# Ad8232_placa_V3.net
KiCad netlist of a schematic drawn in EAGLE
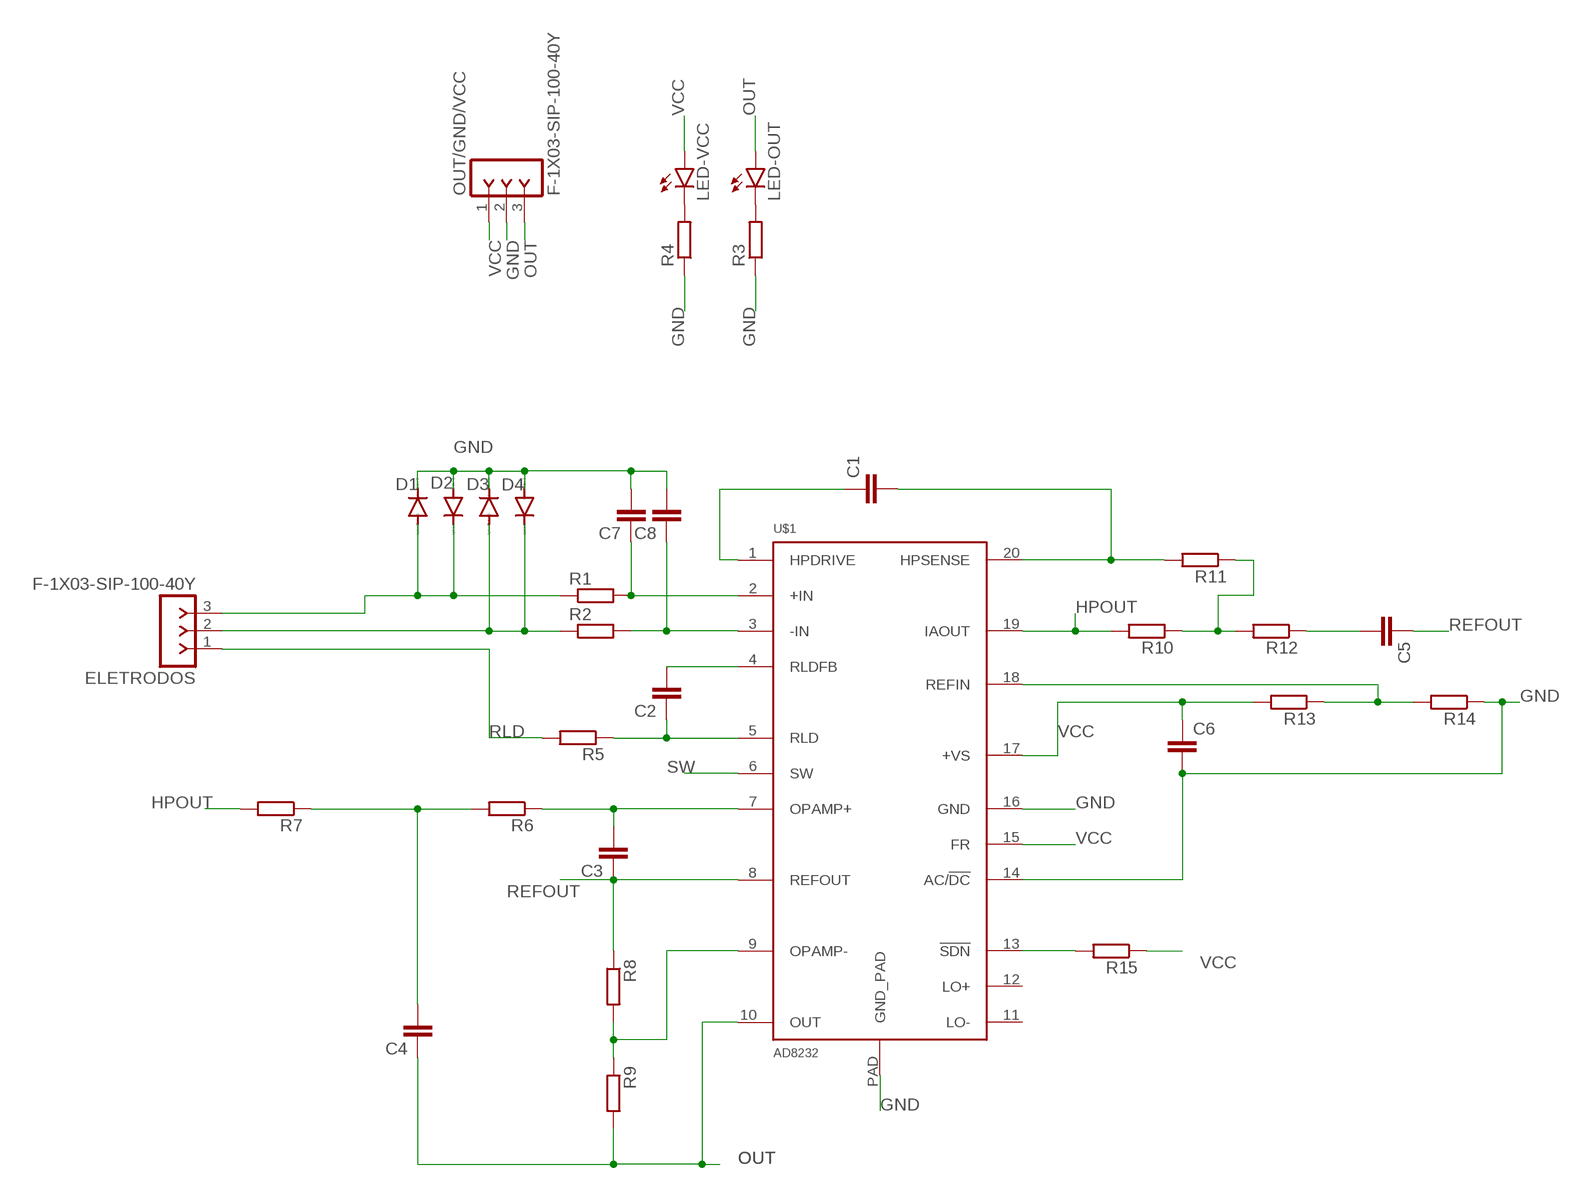
[diagram p0: schematic, sheet 1]

(export (version "E")
  (design (tool "Eeschema 10.0.6"))
  (components
    (comp (ref "C1")
      (value "C-EUC0805")
      (footprint "eagle-import:C0805")
      (libsource (lib "eagle-import") (part "C-EUC0805"))
    )
    (comp (ref "C2")
      (value "C-EUC0805")
      (footprint "eagle-import:C0805")
      (libsource (lib "eagle-import") (part "C-EUC0805"))
    )
    (comp (ref "C3")
      (value "C-EUC0805")
      (footprint "eagle-import:C0805")
      (libsource (lib "eagle-import") (part "C-EUC0805"))
    )
    (comp (ref "C4")
      (value "C-EUC0805")
      (footprint "eagle-import:C0805")
      (libsource (lib "eagle-import") (part "C-EUC0805"))
    )
    (comp (ref "C5")
      (value "C-EUC0805")
      (footprint "eagle-import:C0805")
      (libsource (lib "eagle-import") (part "C-EUC0805"))
    )
    (comp (ref "C6")
      (value "C-EUC0805")
      (footprint "eagle-import:C0805")
      (libsource (lib "eagle-import") (part "C-EUC0805"))
    )
    (comp (ref "C7")
      (value "C-EUC0805")
      (footprint "eagle-import:C0805")
      (libsource (lib "eagle-import") (part "C-EUC0805"))
    )
    (comp (ref "C8")
      (value "C-EUC0805")
      (footprint "eagle-import:C0805")
      (libsource (lib "eagle-import") (part "C-EUC0805"))
    )
    (comp (ref "D1")
      (value "DIODE-MINIMELF")
      (footprint "eagle-import:MINIMELF")
      (libsource (lib "eagle-import") (part "DIODE-MINIMELF"))
    )
    (comp (ref "D2")
      (value "DIODE-MINIMELF")
      (footprint "eagle-import:MINIMELF")
      (libsource (lib "eagle-import") (part "DIODE-MINIMELF"))
    )
    (comp (ref "D3")
      (value "DIODE-MINIMELF")
      (footprint "eagle-import:MINIMELF")
      (libsource (lib "eagle-import") (part "DIODE-MINIMELF"))
    )
    (comp (ref "D4")
      (value "DIODE-MINIMELF")
      (footprint "eagle-import:MINIMELF")
      (libsource (lib "eagle-import") (part "DIODE-MINIMELF"))
    )
    (comp (ref "ELETRODOS")
      (value "F-1X03-SIP-100-40Y")
      (footprint "eagle-import:SIP-100-03-40Y")
      (libsource (lib "eagle-import") (part "F-1X03-SIP-100-40Y"))
    )
    (comp (ref "LED-OUT")
      (value "LEDCHIPLED_0603")
      (footprint "eagle-import:CHIPLED_0603")
      (libsource (lib "eagle-import") (part "LEDCHIPLED_0603"))
    )
    (comp (ref "LED-VCC")
      (value "LEDCHIPLED_0603")
      (footprint "eagle-import:CHIPLED_0603")
      (libsource (lib "eagle-import") (part "LEDCHIPLED_0603"))
    )
    (comp (ref "OUT/GND/VCC")
      (value "F-1X03-SIP-100-40Y")
      (footprint "eagle-import:SIP-100-03-40Y")
      (libsource (lib "eagle-import") (part "F-1X03-SIP-100-40Y"))
    )
    (comp (ref "R1")
      (value "R-EU_R0805")
      (footprint "eagle-import:R0805")
      (libsource (lib "eagle-import") (part "R-EU_R0805"))
    )
    (comp (ref "R2")
      (value "R-EU_R0805")
      (footprint "eagle-import:R0805")
      (libsource (lib "eagle-import") (part "R-EU_R0805"))
    )
    (comp (ref "R3")
      (value "R-EU_R0805")
      (footprint "eagle-import:R0805")
      (libsource (lib "eagle-import") (part "R-EU_R0805"))
    )
    (comp (ref "R4")
      (value "R-EU_R0805")
      (footprint "eagle-import:R0805")
      (libsource (lib "eagle-import") (part "R-EU_R0805"))
    )
    (comp (ref "R5")
      (value "R-EU_R0805")
      (footprint "eagle-import:R0805")
      (libsource (lib "eagle-import") (part "R-EU_R0805"))
    )
    (comp (ref "R6")
      (value "R-EU_R0805")
      (footprint "eagle-import:R0805")
      (libsource (lib "eagle-import") (part "R-EU_R0805"))
    )
    (comp (ref "R7")
      (value "R-EU_R0805")
      (footprint "eagle-import:R0805")
      (libsource (lib "eagle-import") (part "R-EU_R0805"))
    )
    (comp (ref "R8")
      (value "R-EU_R0805")
      (footprint "eagle-import:R0805")
      (libsource (lib "eagle-import") (part "R-EU_R0805"))
    )
    (comp (ref "R9")
      (value "R-EU_R0805")
      (footprint "eagle-import:R0805")
      (libsource (lib "eagle-import") (part "R-EU_R0805"))
    )
    (comp (ref "R10")
      (value "R-EU_R0805")
      (footprint "eagle-import:R0805")
      (libsource (lib "eagle-import") (part "R-EU_R0805"))
    )
    (comp (ref "R11")
      (value "R-EU_R0805")
      (footprint "eagle-import:R0805")
      (libsource (lib "eagle-import") (part "R-EU_R0805"))
    )
    (comp (ref "R12")
      (value "R-EU_R0805")
      (footprint "eagle-import:R0805")
      (libsource (lib "eagle-import") (part "R-EU_R0805"))
    )
    (comp (ref "R13")
      (value "R-EU_R0805")
      (footprint "eagle-import:R0805")
      (libsource (lib "eagle-import") (part "R-EU_R0805"))
    )
    (comp (ref "R14")
      (value "R-EU_R0805")
      (footprint "eagle-import:R0805")
      (libsource (lib "eagle-import") (part "R-EU_R0805"))
    )
    (comp (ref "R15")
      (value "R-EU_R0805")
      (footprint "eagle-import:R0805")
      (libsource (lib "eagle-import") (part "R-EU_R0805"))
    )
    (comp (ref "U$1")
      (value "AD8232")
      (footprint "eagle-import:LFCSP_20")
      (fields (field (name "MF") "Analog Devices"))
      (libsource (lib "eagle-import") (part "AD8232"))
    )
  )
  (nets
    (net (code "1") (name "/GND") (class "Default")
      (node (ref "C6") (pin "2") (pinfunction "2_2") (pintype "passive"))
      (node (ref "C7") (pin "2") (pinfunction "2_2") (pintype "passive"))
      (node (ref "C8") (pin "2") (pinfunction "2_2") (pintype "passive"))
      (node (ref "D1") (pin "C") (pinfunction "C_C") (pintype "passive"))
      (node (ref "D2") (pin "A") (pinfunction "A_A") (pintype "passive"))
      (node (ref "D3") (pin "C") (pinfunction "C_C") (pintype "passive"))
      (node (ref "D4") (pin "A") (pinfunction "A_A") (pintype "passive"))
      (node (ref "OUT/GND/VCC") (pin "2") (pinfunction "2_2") (pintype "passive"))
      (node (ref "R14") (pin "1") (pinfunction "1_1") (pintype "passive"))
      (node (ref "R3") (pin "1") (pinfunction "1_1") (pintype "passive"))
      (node (ref "R4") (pin "1") (pinfunction "1_1") (pintype "passive"))
      (node (ref "U$1") (pin "14") (pinfunction "AC/~{DC}_14") (pintype "bidirectional"))
      (node (ref "U$1") (pin "16") (pinfunction "GND_16") (pintype "bidirectional"))
      (node (ref "U$1") (pin "PAD") (pinfunction "GND_PAD_PAD") (pintype "bidirectional"))
    )
    (net (code "2") (name "/HPOUT") (class "Default")
      (node (ref "R10") (pin "2") (pinfunction "2_2") (pintype "passive"))
      (node (ref "R7") (pin "2") (pinfunction "2_2") (pintype "passive"))
      (node (ref "U$1") (pin "19") (pinfunction "IAOUT_19") (pintype "bidirectional"))
    )
    (net (code "3") (name "/OUT") (class "Default")
      (node (ref "C4") (pin "1") (pinfunction "1_1") (pintype "passive"))
      (node (ref "LED-OUT") (pin "A") (pinfunction "A_A") (pintype "passive"))
      (node (ref "OUT/GND/VCC") (pin "3") (pinfunction "3_3") (pintype "passive"))
      (node (ref "R9") (pin "2") (pinfunction "2_2") (pintype "passive"))
      (node (ref "U$1") (pin "10") (pinfunction "OUT_10") (pintype "bidirectional"))
    )
    (net (code "4") (name "/REFOUT") (class "Default")
      (node (ref "C3") (pin "1") (pinfunction "1_1") (pintype "passive"))
      (node (ref "C5") (pin "1") (pinfunction "1_1") (pintype "passive"))
      (node (ref "R8") (pin "1") (pinfunction "1_1") (pintype "passive"))
      (node (ref "U$1") (pin "8") (pinfunction "REFOUT_8") (pintype "bidirectional"))
    )
    (net (code "5") (name "/RLD") (class "Default")
      (node (ref "ELETRODOS") (pin "1") (pinfunction "1_1") (pintype "passive"))
      (node (ref "R5") (pin "2") (pinfunction "2_2") (pintype "passive"))
    )
    (net (code "6") (name "/SW") (class "Default")
      (node (ref "C5") (pin "2") (pinfunction "2_2") (pintype "passive"))
      (node (ref "R12") (pin "1") (pinfunction "1_1") (pintype "passive"))
      (node (ref "U$1") (pin "6") (pinfunction "SW_6") (pintype "bidirectional"))
    )
    (net (code "7") (name "/VCC") (class "Default")
      (node (ref "C6") (pin "1") (pinfunction "1_1") (pintype "passive"))
      (node (ref "LED-VCC") (pin "A") (pinfunction "A_A") (pintype "passive"))
      (node (ref "OUT/GND/VCC") (pin "1") (pinfunction "1_1") (pintype "passive"))
      (node (ref "R13") (pin "2") (pinfunction "2_2") (pintype "passive"))
      (node (ref "R15") (pin "1") (pinfunction "1_1") (pintype "passive"))
      (node (ref "U$1") (pin "15") (pinfunction "FR_15") (pintype "bidirectional"))
      (node (ref "U$1") (pin "17") (pinfunction "+VS_17") (pintype "bidirectional"))
    )
    (net (code "8") (name "Net-(C4-Pad2)") (class "Default")
      (node (ref "C4") (pin "2") (pinfunction "2_2") (pintype "passive"))
      (node (ref "R6") (pin "2") (pinfunction "2_2") (pintype "passive"))
      (node (ref "R7") (pin "1") (pinfunction "1_1") (pintype "passive"))
    )
    (net (code "9") (name "Net-(D1-PadA)") (class "Default")
      (node (ref "D1") (pin "A") (pinfunction "A_A") (pintype "passive"))
      (node (ref "D2") (pin "C") (pinfunction "C_C") (pintype "passive"))
      (node (ref "ELETRODOS") (pin "3") (pinfunction "3_3") (pintype "passive"))
      (node (ref "R1") (pin "1") (pinfunction "1_1") (pintype "passive"))
    )
    (net (code "10") (name "Net-(D3-PadA)") (class "Default")
      (node (ref "D3") (pin "A") (pinfunction "A_A") (pintype "passive"))
      (node (ref "D4") (pin "C") (pinfunction "C_C") (pintype "passive"))
      (node (ref "ELETRODOS") (pin "2") (pinfunction "2_2") (pintype "passive"))
      (node (ref "R2") (pin "1") (pinfunction "1_1") (pintype "passive"))
    )
    (net (code "11") (name "Net-(LED-OUT-PadC)") (class "Default")
      (node (ref "LED-OUT") (pin "C") (pinfunction "C_C") (pintype "passive"))
      (node (ref "R3") (pin "2") (pinfunction "2_2") (pintype "passive"))
    )
    (net (code "12") (name "Net-(LED-VCC-PadC)") (class "Default")
      (node (ref "LED-VCC") (pin "C") (pinfunction "C_C") (pintype "passive"))
      (node (ref "R4") (pin "2") (pinfunction "2_2") (pintype "passive"))
    )
    (net (code "13") (name "Net-(R10-Pad1)") (class "Default")
      (node (ref "R10") (pin "1") (pinfunction "1_1") (pintype "passive"))
      (node (ref "R11") (pin "1") (pinfunction "1_1") (pintype "passive"))
      (node (ref "R12") (pin "2") (pinfunction "2_2") (pintype "passive"))
    )
    (net (code "14") (name "Net-(U$1-+IN)") (class "Default")
      (node (ref "C7") (pin "1") (pinfunction "1_1") (pintype "passive"))
      (node (ref "R1") (pin "2") (pinfunction "2_2") (pintype "passive"))
      (node (ref "U$1") (pin "2") (pinfunction "+IN_2") (pintype "bidirectional"))
    )
    (net (code "15") (name "Net-(U$1--IN)") (class "Default")
      (node (ref "C8") (pin "1") (pinfunction "1_1") (pintype "passive"))
      (node (ref "R2") (pin "2") (pinfunction "2_2") (pintype "passive"))
      (node (ref "U$1") (pin "3") (pinfunction "-IN_3") (pintype "bidirectional"))
    )
    (net (code "16") (name "Net-(U$1-HPDRIVE)") (class "Default")
      (node (ref "C1") (pin "1") (pinfunction "1_1") (pintype "passive"))
      (node (ref "U$1") (pin "1") (pinfunction "HPDRIVE_1") (pintype "bidirectional"))
    )
    (net (code "17") (name "Net-(U$1-HPSENSE)") (class "Default")
      (node (ref "C1") (pin "2") (pinfunction "2_2") (pintype "passive"))
      (node (ref "R11") (pin "2") (pinfunction "2_2") (pintype "passive"))
      (node (ref "U$1") (pin "20") (pinfunction "HPSENSE_20") (pintype "bidirectional"))
    )
    (net (code "18") (name "Net-(U$1-OPAMP+)") (class "Default")
      (node (ref "C3") (pin "2") (pinfunction "2_2") (pintype "passive"))
      (node (ref "R6") (pin "1") (pinfunction "1_1") (pintype "passive"))
      (node (ref "U$1") (pin "7") (pinfunction "OPAMP+_7") (pintype "bidirectional"))
    )
    (net (code "19") (name "Net-(U$1-OPAMP-)") (class "Default")
      (node (ref "R8") (pin "2") (pinfunction "2_2") (pintype "passive"))
      (node (ref "R9") (pin "1") (pinfunction "1_1") (pintype "passive"))
      (node (ref "U$1") (pin "9") (pinfunction "OPAMP-_9") (pintype "bidirectional"))
    )
    (net (code "20") (name "Net-(U$1-REFIN)") (class "Default")
      (node (ref "R13") (pin "1") (pinfunction "1_1") (pintype "passive"))
      (node (ref "R14") (pin "2") (pinfunction "2_2") (pintype "passive"))
      (node (ref "U$1") (pin "18") (pinfunction "REFIN_18") (pintype "bidirectional"))
    )
    (net (code "21") (name "Net-(U$1-RLD)") (class "Default")
      (node (ref "C2") (pin "1") (pinfunction "1_1") (pintype "passive"))
      (node (ref "R5") (pin "1") (pinfunction "1_1") (pintype "passive"))
      (node (ref "U$1") (pin "5") (pinfunction "RLD_5") (pintype "bidirectional"))
    )
    (net (code "22") (name "Net-(U$1-RLDFB)") (class "Default")
      (node (ref "C2") (pin "2") (pinfunction "2_2") (pintype "passive"))
      (node (ref "U$1") (pin "4") (pinfunction "RLDFB_4") (pintype "bidirectional"))
    )
    (net (code "23") (name "Net-(U$1-~{SDN})") (class "Default")
      (node (ref "R15") (pin "2") (pinfunction "2_2") (pintype "passive"))
      (node (ref "U$1") (pin "13") (pinfunction "~{SDN}_13") (pintype "bidirectional"))
    )
    (net (code "24") (name "unconnected-(U$1-LO+-Pad12)") (class "Default")
      (node (ref "U$1") (pin "12") (pinfunction "LO+_12") (pintype "bidirectional"))
    )
    (net (code "25") (name "unconnected-(U$1-LO--Pad11)") (class "Default")
      (node (ref "U$1") (pin "11") (pinfunction "LO-_11") (pintype "bidirectional"))
    )
  )
)
